# DAI_V1_1.net
KiCad netlist of a schematic drawn in EAGLE
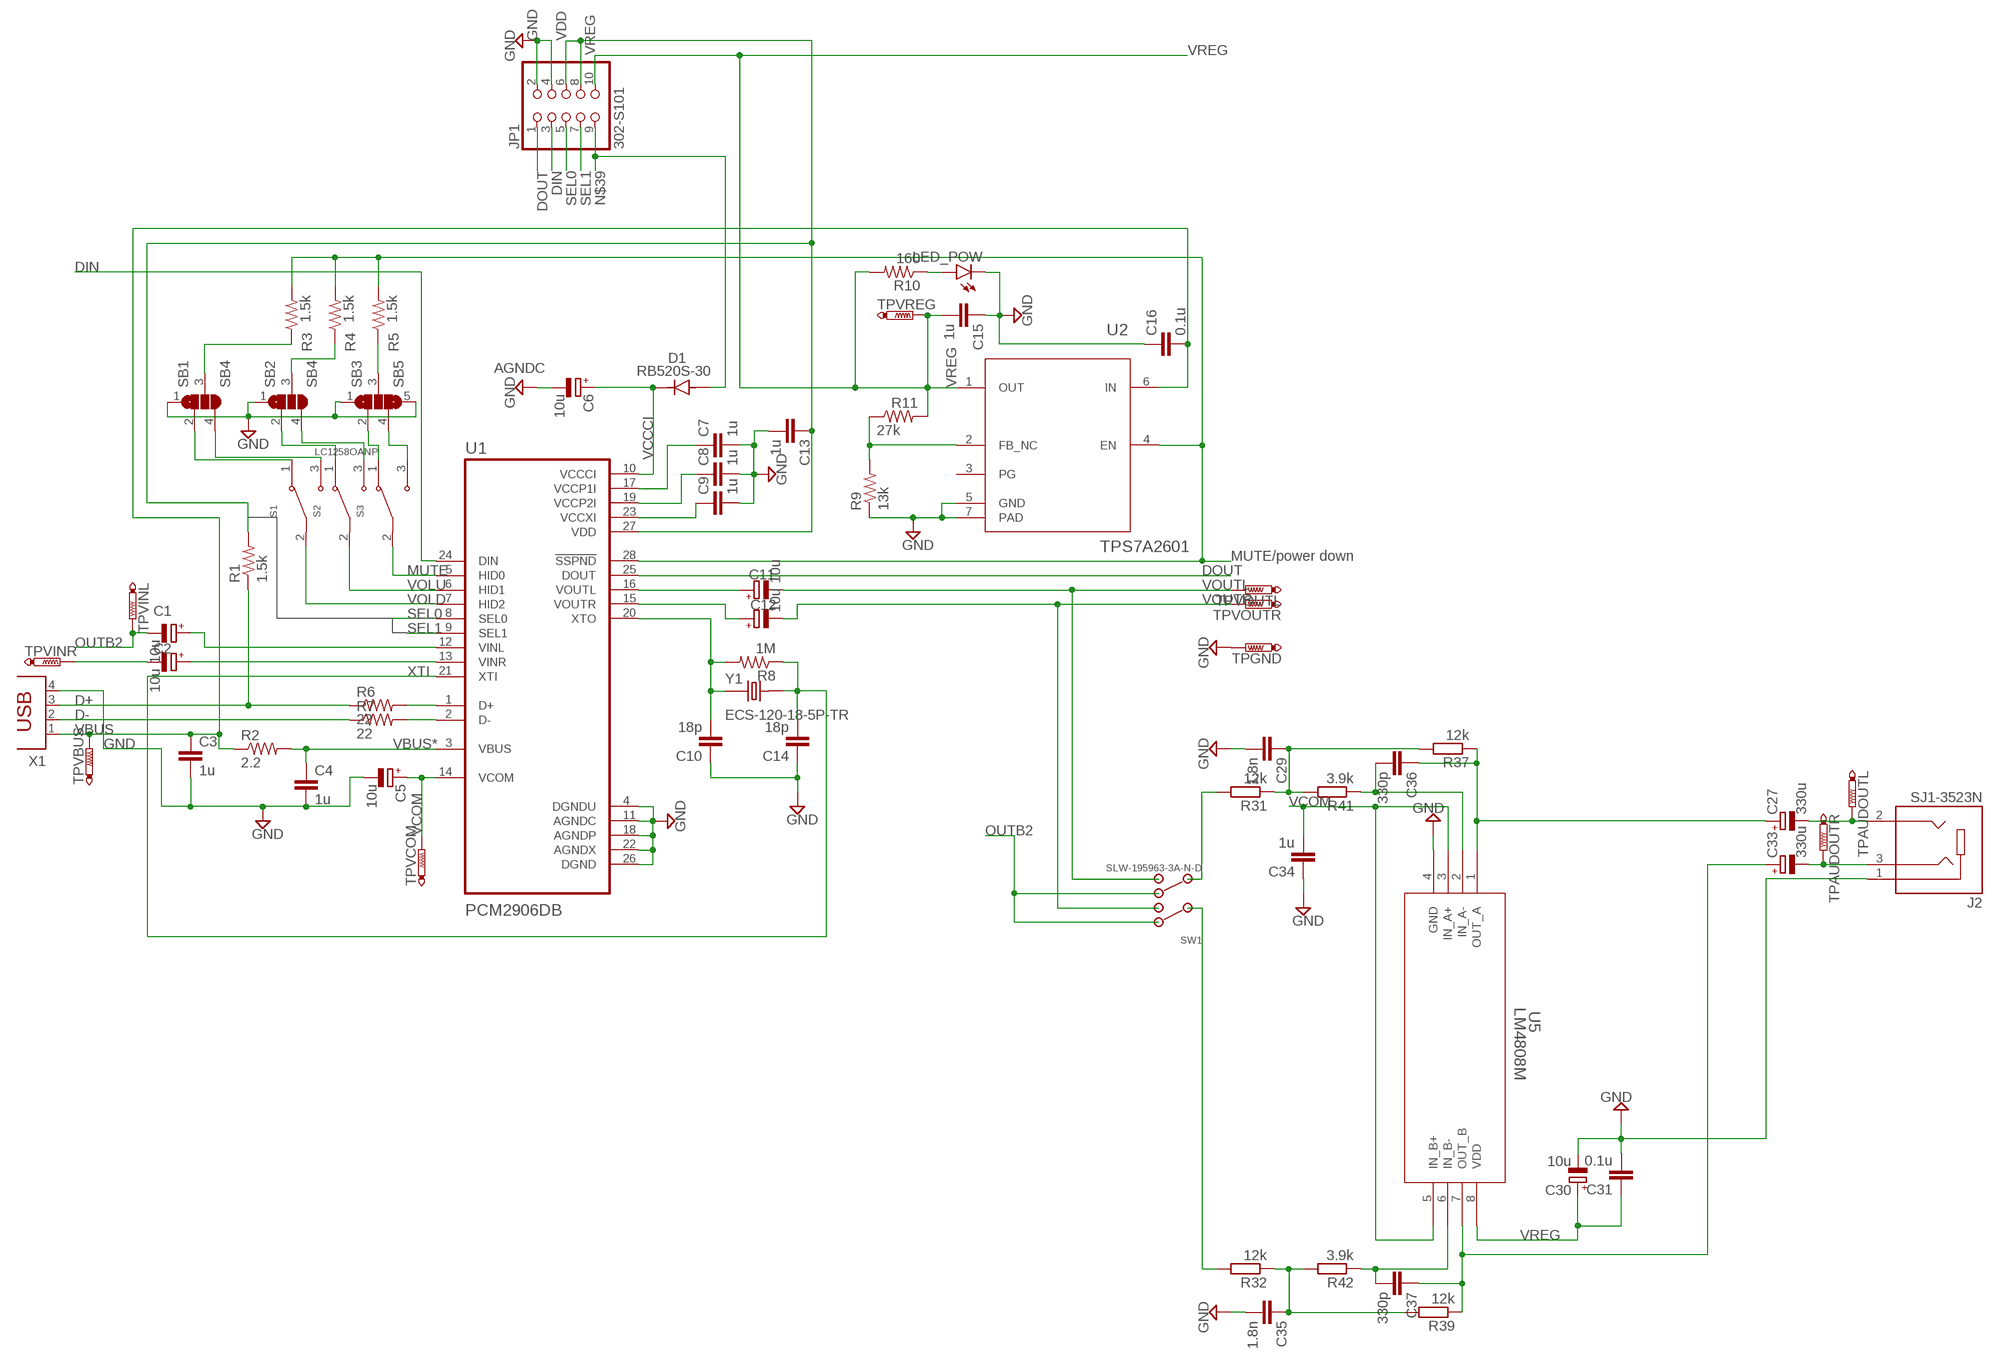
[diagram p0: schematic, sheet 1]
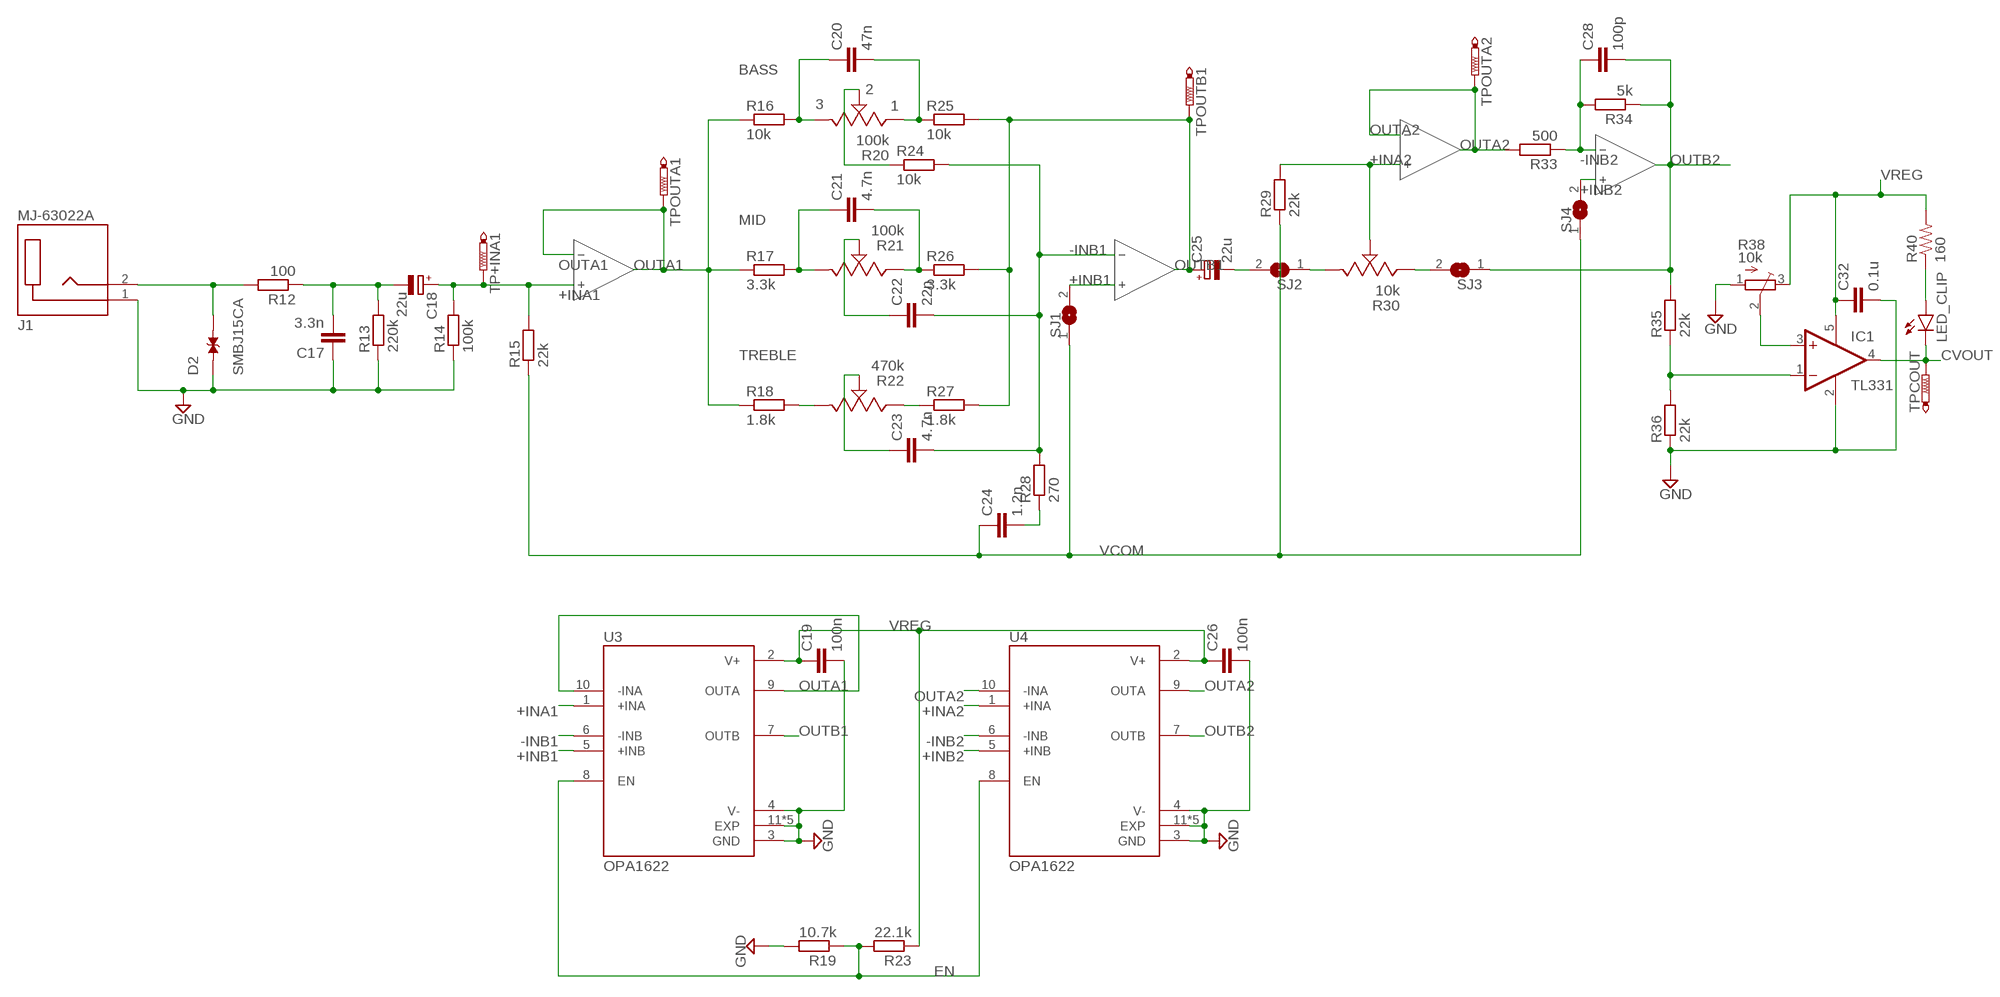
[diagram p1: schematic, sheet 2]

(export (version "E")
  (design (tool "Eeschema 10.0.6"))
  (components
    (comp (ref "C1")
      (value "10u")
      (footprint "eagle-import:PANASONIC_D")
      (libsource (lib "eagle-import") (part "CPOL-EUD"))
    )
    (comp (ref "C2")
      (value "10u")
      (footprint "eagle-import:PANASONIC_D")
      (libsource (lib "eagle-import") (part "CPOL-EUD"))
    )
    (comp (ref "C3")
      (value "1u")
      (footprint "eagle-import:C0805")
      (libsource (lib "eagle-import") (part "C-EUC0805"))
    )
    (comp (ref "C4")
      (value "1u")
      (footprint "eagle-import:C0805")
      (libsource (lib "eagle-import") (part "C-EUC0805"))
    )
    (comp (ref "C5")
      (value "10u")
      (footprint "eagle-import:PANASONIC_B")
      (libsource (lib "eagle-import") (part "CPOL-EUB"))
    )
    (comp (ref "C6")
      (value "10u")
      (footprint "eagle-import:PANASONIC_B")
      (libsource (lib "eagle-import") (part "CPOL-EUB"))
    )
    (comp (ref "C7")
      (value "1u")
      (footprint "eagle-import:C0805")
      (libsource (lib "eagle-import") (part "C-EUC0805"))
    )
    (comp (ref "C8")
      (value "1u")
      (footprint "eagle-import:C0805")
      (libsource (lib "eagle-import") (part "C-EUC0805"))
    )
    (comp (ref "C9")
      (value "1u")
      (footprint "eagle-import:C0805")
      (libsource (lib "eagle-import") (part "C-EUC0805"))
    )
    (comp (ref "C10")
      (value "18p")
      (footprint "eagle-import:C0805")
      (libsource (lib "eagle-import") (part "C-EUC0805"))
    )
    (comp (ref "C11")
      (value "10u")
      (footprint "eagle-import:PANASONIC_D")
      (libsource (lib "eagle-import") (part "CPOL-EUD"))
    )
    (comp (ref "C12")
      (value "10u")
      (footprint "eagle-import:PANASONIC_D")
      (libsource (lib "eagle-import") (part "CPOL-EUD"))
    )
    (comp (ref "C13")
      (value "1u")
      (footprint "eagle-import:C0805")
      (libsource (lib "eagle-import") (part "C-EUC0805"))
    )
    (comp (ref "C14")
      (value "18p")
      (footprint "eagle-import:C0805")
      (libsource (lib "eagle-import") (part "C-EUC0805"))
    )
    (comp (ref "C15")
      (value "1u")
      (footprint "eagle-import:C0805")
      (libsource (lib "eagle-import") (part "C-EUC0805"))
    )
    (comp (ref "C16")
      (value "0.1u")
      (footprint "eagle-import:C0805")
      (libsource (lib "eagle-import") (part "C-EUC0805"))
    )
    (comp (ref "C27")
      (value "330u")
      (footprint "eagle-import:E3,5-10")
      (libsource (lib "eagle-import") (part "CPOL-EUE3.5-10"))
    )
    (comp (ref "C29")
      (value "1.8n")
      (footprint "eagle-import:C1206")
      (libsource (lib "eagle-import") (part "C-EUC1206"))
    )
    (comp (ref "C30")
      (value "10u")
      (footprint "eagle-import:PANASONIC_B")
      (libsource (lib "eagle-import") (part "CPOL-EUB"))
    )
    (comp (ref "C31")
      (value "0.1u")
      (footprint "eagle-import:C0805")
      (libsource (lib "eagle-import") (part "C-EUC0805"))
    )
    (comp (ref "C33")
      (value "330u")
      (footprint "eagle-import:E3,5-10")
      (libsource (lib "eagle-import") (part "CPOL-EUE3.5-10"))
    )
    (comp (ref "C34")
      (value "1u")
      (footprint "eagle-import:C0805")
      (libsource (lib "eagle-import") (part "C-EUC0805"))
    )
    (comp (ref "C35")
      (value "1.8n")
      (footprint "eagle-import:C1206")
      (libsource (lib "eagle-import") (part "C-EUC1206"))
    )
    (comp (ref "C36")
      (value "330p")
      (footprint "eagle-import:C1206")
      (libsource (lib "eagle-import") (part "C-EUC1206"))
    )
    (comp (ref "C37")
      (value "330p")
      (footprint "eagle-import:C1206")
      (libsource (lib "eagle-import") (part "C-EUC1206"))
    )
    (comp (ref "D1")
      (value "RB520S-30")
      (footprint "eagle-import:DIO_RB520S-30")
      (fields (field (name "MF") "Taiwan Semiconductor"))
      (libsource (lib "eagle-import") (part "RB520S-30"))
    )
    (comp (ref "J2")
      (value "SJ1-3523N")
      (footprint "eagle-import:CUI_SJ1-3523N")
      (fields (field (name "MF") "Same Sky"))
      (libsource (lib "eagle-import") (part "SJ1-3523N"))
    )
    (comp (ref "JP1")
      (value "302-S101")
      (footprint "eagle-import:2X05")
      (libsource (lib "eagle-import") (part "PINHD-2X5"))
    )
    (comp (ref "LED_POW")
      (value "LED5MM")
      (footprint "eagle-import:LED5MM")
      (libsource (lib "eagle-import") (part "LED5MM"))
    )
    (comp (ref "R1")
      (value "1.5k")
      (footprint "eagle-import:R0805")
      (libsource (lib "eagle-import") (part "R-US_R0805"))
    )
    (comp (ref "R2")
      (value "2.2")
      (footprint "eagle-import:R0805")
      (libsource (lib "eagle-import") (part "R-US_R0805"))
    )
    (comp (ref "R3")
      (value "1.5k")
      (footprint "eagle-import:R0805")
      (libsource (lib "eagle-import") (part "R-US_R0805"))
    )
    (comp (ref "R4")
      (value "1.5k")
      (footprint "eagle-import:R0805")
      (libsource (lib "eagle-import") (part "R-US_R0805"))
    )
    (comp (ref "R5")
      (value "1.5k")
      (footprint "eagle-import:R0805")
      (libsource (lib "eagle-import") (part "R-US_R0805"))
    )
    (comp (ref "R6")
      (value "22")
      (footprint "eagle-import:R0805")
      (libsource (lib "eagle-import") (part "R-US_R0805"))
    )
    (comp (ref "R7")
      (value "22")
      (footprint "eagle-import:R0805")
      (libsource (lib "eagle-import") (part "R-US_R0805"))
    )
    (comp (ref "R8")
      (value "1M")
      (footprint "eagle-import:R0805")
      (libsource (lib "eagle-import") (part "R-US_R0805"))
    )
    (comp (ref "R9")
      (value "13k")
      (footprint "eagle-import:R0805")
      (libsource (lib "eagle-import") (part "R-US_R0805"))
    )
    (comp (ref "R10")
      (value "160")
      (footprint "eagle-import:R0805")
      (libsource (lib "eagle-import") (part "R-US_R0805"))
    )
    (comp (ref "R11")
      (value "27k")
      (footprint "eagle-import:R0805")
      (libsource (lib "eagle-import") (part "R-US_R0805"))
    )
    (comp (ref "R31")
      (value "12k")
      (footprint "eagle-import:M1206")
      (libsource (lib "eagle-import") (part "R-EU_M1206"))
    )
    (comp (ref "R32")
      (value "12k")
      (footprint "eagle-import:M1206")
      (libsource (lib "eagle-import") (part "R-EU_M1206"))
    )
    (comp (ref "R37")
      (value "12k")
      (footprint "eagle-import:M1206")
      (libsource (lib "eagle-import") (part "R-EU_M1206"))
    )
    (comp (ref "R39")
      (value "12k")
      (footprint "eagle-import:M1206")
      (libsource (lib "eagle-import") (part "R-EU_M1206"))
    )
    (comp (ref "R41")
      (value "3.9k")
      (footprint "eagle-import:M1206")
      (libsource (lib "eagle-import") (part "R-EU_M1206"))
    )
    (comp (ref "R42")
      (value "3.9k")
      (footprint "eagle-import:M1206")
      (libsource (lib "eagle-import") (part "R-EU_M1206"))
    )
    (comp (ref "S1")
      (value "LC1258EENP")
      (footprint "eagle-import:SW_LC1258EENP")
      (fields (field (name "MF") "E-Switch"))
      (libsource (lib "eagle-import") (part "LC1258EENP"))
    )
    (comp (ref "S2")
      (value "LC1258OANP")
      (footprint "eagle-import:SW_LC1258EENP")
      (fields (field (name "MF") "E-Switch") (field (name "MP") "LC1258EENP"))
      (libsource (lib "eagle-import") (part "LC1258EENP"))
    )
    (comp (ref "S3")
      (value "LC1258EENP")
      (footprint "eagle-import:SW_LC1258EENP")
      (fields (field (name "MF") "E-Switch"))
      (libsource (lib "eagle-import") (part "LC1258EENP"))
    )
    (comp (ref "SB1")
      (value "SB4")
      (footprint "eagle-import:SB4")
      (libsource (lib "eagle-import") (part "SB4"))
    )
    (comp (ref "SB2")
      (value "SB4")
      (footprint "eagle-import:SB4")
      (libsource (lib "eagle-import") (part "SB4"))
    )
    (comp (ref "SB3")
      (value "SB5")
      (footprint "eagle-import:SB5")
      (libsource (lib "eagle-import") (part "SB5"))
    )
    (comp (ref "SW1")
      (value "SLW-195963-3A-N-D")
      (footprint "eagle-import:SW-T3-4B-A-A3-S2")
      (libsource (lib "eagle-import") (part "SW-T3-4B-A-A3-S2"))
    )
    (comp (ref "TPAUDOUTL")
      (value "PTR1PAD1-13")
      (footprint "eagle-import:P1-13")
      (libsource (lib "eagle-import") (part "PTR1PAD1-13"))
    )
    (comp (ref "TPAUDOUTR")
      (value "PTR1PAD1-13")
      (footprint "eagle-import:P1-13")
      (libsource (lib "eagle-import") (part "PTR1PAD1-13"))
    )
    (comp (ref "TPGND")
      (value "PTR1PAD1-13")
      (footprint "eagle-import:P1-13")
      (libsource (lib "eagle-import") (part "PTR1PAD1-13"))
    )
    (comp (ref "TPVBUS")
      (value "PTR1PAD1-13")
      (footprint "eagle-import:P1-13")
      (libsource (lib "eagle-import") (part "PTR1PAD1-13"))
    )
    (comp (ref "TPVCOM")
      (value "PTR1PAD1-13")
      (footprint "eagle-import:P1-13")
      (libsource (lib "eagle-import") (part "PTR1PAD1-13"))
    )
    (comp (ref "TPVINL")
      (value "PTR1PAD1-13")
      (footprint "eagle-import:P1-13")
      (libsource (lib "eagle-import") (part "PTR1PAD1-13"))
    )
    (comp (ref "TPVINR")
      (value "PTR1PAD1-13")
      (footprint "eagle-import:P1-13")
      (libsource (lib "eagle-import") (part "PTR1PAD1-13"))
    )
    (comp (ref "TPVOUTL")
      (value "PTR1PAD1-13")
      (footprint "eagle-import:P1-13")
      (libsource (lib "eagle-import") (part "PTR1PAD1-13"))
    )
    (comp (ref "TPVOUTR")
      (value "PTR1PAD1-13")
      (footprint "eagle-import:P1-13")
      (libsource (lib "eagle-import") (part "PTR1PAD1-13"))
    )
    (comp (ref "TPVREG")
      (value "PTR1PAD1-13")
      (footprint "eagle-import:P1-13")
      (libsource (lib "eagle-import") (part "PTR1PAD1-13"))
    )
    (comp (ref "U1")
      (value "PCM2906DB")
      (footprint "eagle-import:SOP65P780X200-28N")
      (fields (field (name "MF") "Texas Instruments"))
      (libsource (lib "eagle-import") (part "PCM2906DB"))
    )
    (comp (ref "U2")
      (value "TPS7A2601")
      (footprint "eagle-import:DRV0006A_NV")
      (fields
        (field (name "MANUFACTURER_PART_NUMBER") "TPS7A2601DRVR")
        (field (name "COPYRIGHT") "Copyright (C) 2025 Ultra Librarian. All rights reserved.")
      )
      (libsource (lib "eagle-import") (part "TPS7A2601DRVRDRV0006A_NV"))
    )
    (comp (ref "U5")
      (value "LM4808M")
      (footprint "eagle-import:M08A")
      (fields
        (field (name "MANUFACTURER_PART_NUMBER") "LM4808M/NOPB")
        (field (name "COPYRIGHT") "Copyright (C) 2025 Ultra Librarian. All rights reserved.")
      )
      (libsource (lib "eagle-import") (part "LM4808M/NOPB"))
    )
    (comp (ref "X1")
      (value "PN61729")
      (footprint "eagle-import:PN61729")
      (libsource (lib "eagle-import") (part "PN61729"))
    )
    (comp (ref "Y1")
      (value "ECS-120-18-5P-TR")
      (footprint "eagle-import:XTAL_ECS-120-18-5P-TR")
      (fields (field (name "MF") "ECS International"))
      (libsource (lib "eagle-import") (part "ECS-120-18-5P-TR"))
    )
    (comp (ref "C17")
      (value "3.3n")
      (footprint "eagle-import:C1206")
      (libsource (lib "eagle-import") (part "C-EUC1206"))
    )
    (comp (ref "C18")
      (value "22u")
      (footprint "eagle-import:PANASONIC_D")
      (libsource (lib "eagle-import") (part "CPOL-EUD"))
    )
    (comp (ref "C19")
      (value "100n")
      (footprint "eagle-import:C0805")
      (libsource (lib "eagle-import") (part "C-EUC0805"))
    )
    (comp (ref "C20")
      (value "47n")
      (footprint "eagle-import:C1206")
      (libsource (lib "eagle-import") (part "C-EUC1206"))
    )
    (comp (ref "C21")
      (value "4.7n")
      (footprint "eagle-import:C1206")
      (libsource (lib "eagle-import") (part "C-EUC1206"))
    )
    (comp (ref "C22")
      (value "22n")
      (footprint "eagle-import:C1206")
      (libsource (lib "eagle-import") (part "C-EUC1206"))
    )
    (comp (ref "C23")
      (value "4.7n")
      (footprint "eagle-import:C1206")
      (libsource (lib "eagle-import") (part "C-EUC1206"))
    )
    (comp (ref "C24")
      (value "1.2n")
      (footprint "eagle-import:C1206")
      (libsource (lib "eagle-import") (part "C-EUC1206"))
    )
    (comp (ref "C25")
      (value "22u")
      (footprint "eagle-import:PANASONIC_D")
      (libsource (lib "eagle-import") (part "CPOL-EUD"))
    )
    (comp (ref "C26")
      (value "100n")
      (footprint "eagle-import:C0805")
      (libsource (lib "eagle-import") (part "C-EUC0805"))
    )
    (comp (ref "C28")
      (value "100p")
      (footprint "eagle-import:C1206")
      (libsource (lib "eagle-import") (part "C-EUC1206"))
    )
    (comp (ref "C32")
      (value "0.1u")
      (footprint "eagle-import:C0805")
      (libsource (lib "eagle-import") (part "C-EUC0805"))
    )
    (comp (ref "D2")
      (value "SMBJ15CA")
      (footprint "eagle-import:DIOM4336X265N")
      (fields (field (name "MF") "Taiwan Semiconductor"))
      (libsource (lib "eagle-import") (part "SMBJ15CA"))
    )
    (comp (ref "IC1")
      (value "TL331")
      (footprint "eagle-import:DBV-R-PDSO-G5")
      (libsource (lib "eagle-import") (part "TL331"))
    )
    (comp (ref "J1")
      (value "MJ-63022A")
      (footprint "eagle-import:CUI_MJ-63022A")
      (fields (field (name "MF") "Same Sky"))
      (libsource (lib "eagle-import") (part "MJ-63022A"))
    )
    (comp (ref "LED_CLIP")
      (value "LED5MM")
      (footprint "eagle-import:LED5MM")
      (libsource (lib "eagle-import") (part "LED5MM"))
    )
    (comp (ref "R12")
      (value "100")
      (footprint "eagle-import:M1206")
      (libsource (lib "eagle-import") (part "R-EU_M1206"))
    )
    (comp (ref "R13")
      (value "220k")
      (footprint "eagle-import:M1206")
      (libsource (lib "eagle-import") (part "R-EU_M1206"))
    )
    (comp (ref "R14")
      (value "100k")
      (footprint "eagle-import:M1206")
      (libsource (lib "eagle-import") (part "R-EU_M1206"))
    )
    (comp (ref "R15")
      (value "22k")
      (footprint "eagle-import:M1206")
      (libsource (lib "eagle-import") (part "R-EU_M1206"))
    )
    (comp (ref "R16")
      (value "10k")
      (footprint "eagle-import:M1206")
      (libsource (lib "eagle-import") (part "R-EU_M1206"))
    )
    (comp (ref "R17")
      (value "3.3k")
      (footprint "eagle-import:M1206")
      (libsource (lib "eagle-import") (part "R-EU_M1206"))
    )
    (comp (ref "R18")
      (value "1.8k")
      (footprint "eagle-import:M1206")
      (libsource (lib "eagle-import") (part "R-EU_M1206"))
    )
    (comp (ref "R19")
      (value "10.7k")
      (footprint "eagle-import:R1206")
      (libsource (lib "eagle-import") (part "R-EU_R1206"))
    )
    (comp (ref "R20")
      (value "100k")
      (footprint "eagle-import:POT_PTN16-A100125K1B1")
      (fields (field (name "MF") "Same Sky") (field (name "MP") "PTN16-A100125K1B1"))
      (libsource (lib "eagle-import") (part "PTN16-A100125K1B1"))
    )
    (comp (ref "R21")
      (value "100k")
      (footprint "eagle-import:POT_PTN16-A100125K1B1")
      (fields (field (name "MF") "Same Sky") (field (name "MP") "PTN16-A100125K1B1"))
      (libsource (lib "eagle-import") (part "PTN16-A100125K1B1"))
    )
    (comp (ref "R22")
      (value "470k")
      (footprint "eagle-import:POT_PTN16-A100125K1B1")
      (fields (field (name "MF") "Same Sky") (field (name "MP") "PTN16-A100125K1B1"))
      (libsource (lib "eagle-import") (part "PTN16-A100125K1B1"))
    )
    (comp (ref "R23")
      (value "22.1k")
      (footprint "eagle-import:R1206")
      (libsource (lib "eagle-import") (part "R-EU_R1206"))
    )
    (comp (ref "R24")
      (value "10k")
      (footprint "eagle-import:M1206")
      (libsource (lib "eagle-import") (part "R-EU_M1206"))
    )
    (comp (ref "R25")
      (value "10k")
      (footprint "eagle-import:M1206")
      (libsource (lib "eagle-import") (part "R-EU_M1206"))
    )
    (comp (ref "R26")
      (value "3.3k")
      (footprint "eagle-import:M1206")
      (libsource (lib "eagle-import") (part "R-EU_M1206"))
    )
    (comp (ref "R27")
      (value "1.8k")
      (footprint "eagle-import:M1206")
      (libsource (lib "eagle-import") (part "R-EU_M1206"))
    )
    (comp (ref "R28")
      (value "270")
      (footprint "eagle-import:M1206")
      (libsource (lib "eagle-import") (part "R-EU_M1206"))
    )
    (comp (ref "R29")
      (value "22k")
      (footprint "eagle-import:M1206")
      (libsource (lib "eagle-import") (part "R-EU_M1206"))
    )
    (comp (ref "R30")
      (value "10k")
      (footprint "eagle-import:POT_PTN16-A100125K1B1")
      (fields (field (name "MF") "Same Sky") (field (name "MP") "PTN16-A100125K1B1"))
      (libsource (lib "eagle-import") (part "PTN16-A100125K1B1"))
    )
    (comp (ref "R33")
      (value "500")
      (footprint "eagle-import:M1206")
      (libsource (lib "eagle-import") (part "R-EU_M1206"))
    )
    (comp (ref "R34")
      (value "5k")
      (footprint "eagle-import:M1206")
      (libsource (lib "eagle-import") (part "R-EU_M1206"))
    )
    (comp (ref "R35")
      (value "22k")
      (footprint "eagle-import:M1206")
      (libsource (lib "eagle-import") (part "R-EU_M1206"))
    )
    (comp (ref "R36")
      (value "22k")
      (footprint "eagle-import:M1206")
      (libsource (lib "eagle-import") (part "R-EU_M1206"))
    )
    (comp (ref "R38")
      (value "10k")
      (footprint "eagle-import:601030_AVX")
      (fields
        (field (name "MANUFACTURER_PART_NUMBER") "601030")
        (field (name "COPYRIGHT") "Copyright (C) 2025 Ultra Librarian. All rights reserved.")
      )
      (libsource (lib "eagle-import") (part "601030"))
    )
    (comp (ref "R40")
      (value "160")
      (footprint "eagle-import:R0805")
      (libsource (lib "eagle-import") (part "R-US_R0805"))
    )
    (comp (ref "SJ1")
      (value "SJW")
      (footprint "eagle-import:SJW")
      (libsource (lib "eagle-import") (part "SJW"))
    )
    (comp (ref "SJ2")
      (value "SJW")
      (footprint "eagle-import:SJW")
      (libsource (lib "eagle-import") (part "SJW"))
    )
    (comp (ref "SJ3")
      (value "SJW")
      (footprint "eagle-import:SJW")
      (libsource (lib "eagle-import") (part "SJW"))
    )
    (comp (ref "SJ4")
      (value "SJW")
      (footprint "eagle-import:SJW")
      (libsource (lib "eagle-import") (part "SJW"))
    )
    (comp (ref "TP+INA1")
      (value "PTR1PAD1-13")
      (footprint "eagle-import:P1-13")
      (libsource (lib "eagle-import") (part "PTR1PAD1-13"))
    )
    (comp (ref "TPCOUT")
      (value "PTR1PAD1-13")
      (footprint "eagle-import:P1-13")
      (libsource (lib "eagle-import") (part "PTR1PAD1-13"))
    )
    (comp (ref "TPOUTA1")
      (value "PTR1PAD1-13")
      (footprint "eagle-import:P1-13")
      (libsource (lib "eagle-import") (part "PTR1PAD1-13"))
    )
    (comp (ref "TPOUTA2")
      (value "PTR1PAD1-13")
      (footprint "eagle-import:P1-13")
      (libsource (lib "eagle-import") (part "PTR1PAD1-13"))
    )
    (comp (ref "TPOUTB1")
      (value "PTR1PAD1-13")
      (footprint "eagle-import:P1-13")
      (libsource (lib "eagle-import") (part "PTR1PAD1-13"))
    )
    (comp (ref "U3")
      (value "OPA1622")
      (footprint "eagle-import:IC_OPA1622IDRCR")
      (fields (field (name "MF") "Texas Instruments") (field (name "MP") "OPA1622IDRCR"))
      (libsource (lib "eagle-import") (part "OPA1622IDRCR"))
    )
    (comp (ref "U4")
      (value "OPA1622")
      (footprint "eagle-import:IC_OPA1622IDRCR")
      (fields (field (name "MF") "Texas Instruments") (field (name "MP") "OPA1622IDRCR"))
      (libsource (lib "eagle-import") (part "OPA1622IDRCR"))
    )
  )
  (nets
    (net (code "1") (name "+INA1") (class "Default")
      (node (ref "C18") (pin "+") (pinfunction "+_+") (pintype "passive"))
      (node (ref "R14") (pin "2") (pinfunction "2_2") (pintype "passive"))
      (node (ref "R15") (pin "2") (pinfunction "2_2") (pintype "passive"))
      (node (ref "TP+INA1") (pin "TP") (pinfunction "TP_TP") (pintype "input"))
      (node (ref "U3") (pin "1") (pinfunction "+INA_1") (pintype "input"))
    )
    (net (code "2") (name "+INA2") (class "Default")
      (node (ref "R29") (pin "2") (pinfunction "2_2") (pintype "passive"))
      (node (ref "R30") (pin "2") (pinfunction "2_2") (pintype "passive"))
      (node (ref "U4") (pin "1") (pinfunction "+INA_1") (pintype "input"))
    )
    (net (code "3") (name "+INB1") (class "Default")
      (node (ref "SJ1") (pin "2") (pinfunction "2_2") (pintype "passive"))
      (node (ref "U3") (pin "5") (pinfunction "+INB_5") (pintype "input"))
    )
    (net (code "4") (name "+INB2") (class "Default")
      (node (ref "SJ4") (pin "2") (pinfunction "2_2") (pintype "passive"))
      (node (ref "U4") (pin "5") (pinfunction "+INB_5") (pintype "input"))
    )
    (net (code "5") (name "-INB1") (class "Default")
      (node (ref "C22") (pin "2") (pinfunction "2_2") (pintype "passive"))
      (node (ref "C23") (pin "2") (pinfunction "2_2") (pintype "passive"))
      (node (ref "R24") (pin "2") (pinfunction "2_2") (pintype "passive"))
      (node (ref "R28") (pin "2") (pinfunction "2_2") (pintype "passive"))
      (node (ref "U3") (pin "6") (pinfunction "-INB_6") (pintype "input"))
    )
    (net (code "6") (name "-INB2") (class "Default")
      (node (ref "C28") (pin "1") (pinfunction "1_1") (pintype "passive"))
      (node (ref "R33") (pin "1") (pinfunction "1_1") (pintype "passive"))
      (node (ref "R34") (pin "2") (pinfunction "2_2") (pintype "passive"))
      (node (ref "U4") (pin "6") (pinfunction "-INB_6") (pintype "input"))
    )
    (net (code "7") (name "CVOUT") (class "Default")
      (node (ref "IC1") (pin "4") (pinfunction "OUT_4") (pintype "output"))
      (node (ref "LED_CLIP") (pin "K") (pinfunction "C_K") (pintype "passive"))
      (node (ref "TPCOUT") (pin "TP") (pinfunction "TP_TP") (pintype "input"))
    )
    (net (code "8") (name "D+") (class "Default")
      (node (ref "R1") (pin "1") (pinfunction "1_1") (pintype "passive"))
      (node (ref "R6") (pin "1") (pinfunction "1_1") (pintype "passive"))
      (node (ref "X1") (pin "3") (pinfunction "3_3") (pintype "passive"))
    )
    (net (code "9") (name "D-") (class "Default")
      (node (ref "R7") (pin "1") (pinfunction "1_1") (pintype "passive"))
      (node (ref "X1") (pin "2") (pinfunction "2_2") (pintype "passive"))
    )
    (net (code "10") (name "DIN") (class "Default")
      (node (ref "JP1") (pin "3") (pinfunction "3_3") (pintype "passive"))
      (node (ref "U1") (pin "24") (pinfunction "DIN_24") (pintype "input"))
    )
    (net (code "11") (name "DOUT") (class "Default")
      (node (ref "JP1") (pin "1") (pinfunction "1_1") (pintype "passive"))
      (node (ref "U1") (pin "25") (pinfunction "DOUT_25") (pintype "output"))
    )
    (net (code "12") (name "EN") (class "Default")
      (node (ref "R19") (pin "1") (pinfunction "1_1") (pintype "passive"))
      (node (ref "R23") (pin "2") (pinfunction "2_2") (pintype "passive"))
      (node (ref "U3") (pin "8") (pinfunction "EN_8") (pintype "input"))
      (node (ref "U4") (pin "8") (pinfunction "EN_8") (pintype "input"))
    )
    (net (code "13") (name "GND") (class "Default")
      (node (ref "C10") (pin "1") (pinfunction "1_1") (pintype "passive"))
      (node (ref "C13") (pin "2") (pinfunction "2_2") (pintype "passive"))
      (node (ref "C14") (pin "1") (pinfunction "1_1") (pintype "passive"))
      (node (ref "C15") (pin "1") (pinfunction "1_1") (pintype "passive"))
      (node (ref "C16") (pin "1") (pinfunction "1_1") (pintype "passive"))
      (node (ref "C17") (pin "1") (pinfunction "1_1") (pintype "passive"))
      (node (ref "C19") (pin "2") (pinfunction "2_2") (pintype "passive"))
      (node (ref "C26") (pin "2") (pinfunction "2_2") (pintype "passive"))
      (node (ref "C29") (pin "2") (pinfunction "2_2") (pintype "passive"))
      (node (ref "C3") (pin "2") (pinfunction "2_2") (pintype "passive"))
      (node (ref "C30") (pin "-") (pinfunction "-_-") (pintype "passive"))
      (node (ref "C31") (pin "2") (pinfunction "2_2") (pintype "passive"))
      (node (ref "C32") (pin "2") (pinfunction "2_2") (pintype "passive"))
      (node (ref "C34") (pin "1") (pinfunction "1_1") (pintype "passive"))
      (node (ref "C35") (pin "2") (pinfunction "2_2") (pintype "passive"))
      (node (ref "C4") (pin "2") (pinfunction "2_2") (pintype "passive"))
      (node (ref "C5") (pin "-") (pinfunction "-_-") (pintype "passive"))
      (node (ref "C6") (pin "-") (pinfunction "-_-") (pintype "passive"))
      (node (ref "C7") (pin "2") (pinfunction "2_2") (pintype "passive"))
      (node (ref "C8") (pin "2") (pinfunction "2_2") (pintype "passive"))
      (node (ref "C9") (pin "2") (pinfunction "2_2") (pintype "passive"))
      (node (ref "D2") (pin "1") (pinfunction "1_1") (pintype "passive"))
      (node (ref "IC1") (pin "2") (pinfunction "GND_2") (pintype "power_in"))
      (node (ref "J1") (pin "1") (pinfunction "SLEEVE_1") (pintype "passive"))
      (node (ref "J2") (pin "1") (pinfunction "1_1") (pintype "passive"))
      (node (ref "JP1") (pin "2") (pinfunction "2_2") (pintype "passive"))
      (node (ref "JP1") (pin "4") (pinfunction "4_4") (pintype "passive"))
      (node (ref "LED_POW") (pin "K") (pinfunction "C_K") (pintype "passive"))
      (node (ref "R13") (pin "1") (pinfunction "1_1") (pintype "passive"))
      (node (ref "R14") (pin "1") (pinfunction "1_1") (pintype "passive"))
      (node (ref "R19") (pin "2") (pinfunction "2_2") (pintype "passive"))
      (node (ref "R36") (pin "1") (pinfunction "1_1") (pintype "passive"))
      (node (ref "R38") (pin "1") (pinfunction "A_1") (pintype "passive"))
      (node (ref "R9") (pin "1") (pinfunction "1_1") (pintype "passive"))
      (node (ref "SB1") (pin "1") (pinfunction "1_1") (pintype "passive"))
      (node (ref "SB2") (pin "1") (pinfunction "1_1") (pintype "passive"))
      (node (ref "SB3") (pin "1") (pinfunction "1_1") (pintype "passive"))
      (node (ref "SB3") (pin "5") (pinfunction "5_5") (pintype "passive"))
      (node (ref "TPGND") (pin "TP") (pinfunction "TP_TP") (pintype "input"))
      (node (ref "U1") (pin "11") (pinfunction "AGNDC_11") (pintype "power_in"))
      (node (ref "U1") (pin "18") (pinfunction "AGNDP_18") (pintype "power_in"))
      (node (ref "U1") (pin "22") (pinfunction "AGNDX_22") (pintype "power_in"))
      (node (ref "U1") (pin "26") (pinfunction "DGND_26") (pintype "power_in"))
      (node (ref "U1") (pin "4") (pinfunction "DGNDU_4") (pintype "power_in"))
      (node (ref "U2") (pin "5") (pinfunction "GND_5") (pintype "power_in"))
      (node (ref "U2") (pin "7") (pinfunction "PAD_7") (pintype "passive"))
      (node (ref "U3") (pin "11") (pinfunction "EXP_11") (pintype "power_in"))
      (node (ref "U3") (pin "12") (pinfunction "EXP_12") (pintype "power_in"))
      (node (ref "U3") (pin "13") (pinfunction "EXP_13") (pintype "power_in"))
      (node (ref "U3") (pin "14") (pinfunction "EXP_14") (pintype "power_in"))
      (node (ref "U3") (pin "15") (pinfunction "EXP_15") (pintype "power_in"))
      (node (ref "U3") (pin "3") (pinfunction "GND_3") (pintype "power_in"))
      (node (ref "U3") (pin "4") (pinfunction "V-_4") (pintype "power_in"))
      (node (ref "U4") (pin "11") (pinfunction "EXP_11") (pintype "power_in"))
      (node (ref "U4") (pin "12") (pinfunction "EXP_12") (pintype "power_in"))
      (node (ref "U4") (pin "13") (pinfunction "EXP_13") (pintype "power_in"))
      (node (ref "U4") (pin "14") (pinfunction "EXP_14") (pintype "power_in"))
      (node (ref "U4") (pin "15") (pinfunction "EXP_15") (pintype "power_in"))
      (node (ref "U4") (pin "3") (pinfunction "GND_3") (pintype "power_in"))
      (node (ref "U4") (pin "4") (pinfunction "V-_4") (pintype "power_in"))
      (node (ref "U5") (pin "4") (pinfunction "GND_4") (pintype "power_in"))
      (node (ref "X1") (pin "4") (pinfunction "4_4") (pintype "passive"))
    )
    (net (code "14") (name "MUTE") (class "Default")
      (node (ref "S3") (pin "2") (pinfunction "COM_2") (pintype "passive"))
      (node (ref "U1") (pin "5") (pinfunction "HID0_5") (pintype "input"))
    )
    (net (code "15") (name "N$39") (class "Default")
      (node (ref "D1") (pin "A") (pinfunction "A_A") (pintype "passive"))
      (node (ref "JP1") (pin "9") (pinfunction "9_9") (pintype "passive"))
    )
    (net (code "16") (name "Net-(C2-Pad-)") (class "Default")
      (node (ref "C2") (pin "-") (pinfunction "-_-") (pintype "passive"))
      (node (ref "TPVINR") (pin "TP") (pinfunction "TP_TP") (pintype "input"))
    )
    (net (code "17") (name "Net-(C17-Pad2)") (class "Default")
      (node (ref "C17") (pin "2") (pinfunction "2_2") (pintype "passive"))
      (node (ref "C18") (pin "-") (pinfunction "-_-") (pintype "passive"))
      (node (ref "R12") (pin "1") (pinfunction "1_1") (pintype "passive"))
      (node (ref "R13") (pin "2") (pinfunction "2_2") (pintype "passive"))
    )
    (net (code "18") (name "Net-(C20-Pad1)") (class "Default")
      (node (ref "C20") (pin "1") (pinfunction "1_1") (pintype "passive"))
      (node (ref "R16") (pin "2") (pinfunction "2_2") (pintype "passive"))
      (node (ref "R20") (pin "3") (pinfunction "3_3") (pintype "passive"))
    )
    (net (code "19") (name "Net-(C20-Pad2)") (class "Default")
      (node (ref "C20") (pin "2") (pinfunction "2_2") (pintype "passive"))
      (node (ref "R20") (pin "1") (pinfunction "1_1") (pintype "passive"))
      (node (ref "R25") (pin "1") (pinfunction "1_1") (pintype "passive"))
    )
    (net (code "20") (name "Net-(C21-Pad1)") (class "Default")
      (node (ref "C21") (pin "1") (pinfunction "1_1") (pintype "passive"))
      (node (ref "R17") (pin "2") (pinfunction "2_2") (pintype "passive"))
      (node (ref "R21") (pin "3") (pinfunction "3_3") (pintype "passive"))
    )
    (net (code "21") (name "Net-(C21-Pad2)") (class "Default")
      (node (ref "C21") (pin "2") (pinfunction "2_2") (pintype "passive"))
      (node (ref "R21") (pin "1") (pinfunction "1_1") (pintype "passive"))
      (node (ref "R26") (pin "1") (pinfunction "1_1") (pintype "passive"))
    )
    (net (code "22") (name "Net-(C22-Pad1)") (class "Default")
      (node (ref "C22") (pin "1") (pinfunction "1_1") (pintype "passive"))
      (node (ref "R21") (pin "2") (pinfunction "2_2") (pintype "passive"))
    )
    (net (code "23") (name "Net-(C23-Pad1)") (class "Default")
      (node (ref "C23") (pin "1") (pinfunction "1_1") (pintype "passive"))
      (node (ref "R22") (pin "2") (pinfunction "2_2") (pintype "passive"))
    )
    (net (code "24") (name "Net-(C24-Pad2)") (class "Default")
      (node (ref "C24") (pin "2") (pinfunction "2_2") (pintype "passive"))
      (node (ref "R28") (pin "1") (pinfunction "1_1") (pintype "passive"))
    )
    (net (code "25") (name "Net-(C25-Pad-)") (class "Default")
      (node (ref "C25") (pin "-") (pinfunction "-_-") (pintype "passive"))
      (node (ref "SJ2") (pin "2") (pinfunction "2_2") (pintype "passive"))
    )
    (net (code "26") (name "Net-(C27-Pad-)") (class "Default")
      (node (ref "C27") (pin "-") (pinfunction "-_-") (pintype "passive"))
      (node (ref "J2") (pin "2") (pinfunction "2_2") (pintype "passive"))
      (node (ref "TPAUDOUTL") (pin "TP") (pinfunction "TP_TP") (pintype "input"))
    )
    (net (code "27") (name "Net-(C29-Pad1)") (class "Default")
      (node (ref "C29") (pin "1") (pinfunction "1_1") (pintype "passive"))
      (node (ref "R31") (pin "1") (pinfunction "1_1") (pintype "passive"))
      (node (ref "R37") (pin "2") (pinfunction "2_2") (pintype "passive"))
      (node (ref "R41") (pin "2") (pinfunction "2_2") (pintype "passive"))
    )
    (net (code "28") (name "Net-(C33-Pad-)") (class "Default")
      (node (ref "C33") (pin "-") (pinfunction "-_-") (pintype "passive"))
      (node (ref "J2") (pin "3") (pinfunction "3_3") (pintype "passive"))
      (node (ref "TPAUDOUTR") (pin "TP") (pinfunction "TP_TP") (pintype "input"))
    )
    (net (code "29") (name "Net-(C35-Pad1)") (class "Default")
      (node (ref "C35") (pin "1") (pinfunction "1_1") (pintype "passive"))
      (node (ref "R32") (pin "1") (pinfunction "1_1") (pintype "passive"))
      (node (ref "R39") (pin "2") (pinfunction "2_2") (pintype "passive"))
      (node (ref "R42") (pin "2") (pinfunction "2_2") (pintype "passive"))
    )
    (net (code "30") (name "Net-(IC1-+IN)") (class "Default")
      (node (ref "IC1") (pin "3") (pinfunction "+IN_3") (pintype "input"))
      (node (ref "R38") (pin "2") (pinfunction "S_2") (pintype "passive"))
    )
    (net (code "31") (name "Net-(IC1--IN)") (class "Default")
      (node (ref "IC1") (pin "1") (pinfunction "-IN_1") (pintype "input"))
      (node (ref "R35") (pin "1") (pinfunction "1_1") (pintype "passive"))
      (node (ref "R36") (pin "2") (pinfunction "2_2") (pintype "passive"))
    )
    (net (code "32") (name "Net-(J1-TIP)") (class "Default")
      (node (ref "D2") (pin "2") (pinfunction "2_2") (pintype "passive"))
      (node (ref "J1") (pin "2") (pinfunction "TIP_2") (pintype "passive"))
      (node (ref "R12") (pin "2") (pinfunction "2_2") (pintype "passive"))
    )
    (net (code "33") (name "Net-(LED_CLIP-PadA)") (class "Default")
      (node (ref "LED_CLIP") (pin "A") (pinfunction "A_A") (pintype "passive"))
      (node (ref "R40") (pin "1") (pinfunction "1_1") (pintype "passive"))
    )
    (net (code "34") (name "Net-(LED_POW-PadA)") (class "Default")
      (node (ref "LED_POW") (pin "A") (pinfunction "A_A") (pintype "passive"))
      (node (ref "R10") (pin "1") (pinfunction "1_1") (pintype "passive"))
    )
    (net (code "35") (name "Net-(R3-Pad1)") (class "Default")
      (node (ref "R3") (pin "1") (pinfunction "1_1") (pintype "passive"))
      (node (ref "SB1") (pin "3") (pinfunction "3_3") (pintype "passive"))
    )
    (net (code "36") (name "Net-(R4-Pad1)") (class "Default")
      (node (ref "R4") (pin "1") (pinfunction "1_1") (pintype "passive"))
      (node (ref "SB2") (pin "3") (pinfunction "3_3") (pintype "passive"))
    )
    (net (code "37") (name "Net-(R5-Pad1)") (class "Default")
      (node (ref "R5") (pin "1") (pinfunction "1_1") (pintype "passive"))
      (node (ref "SB3") (pin "3") (pinfunction "3_3") (pintype "passive"))
    )
    (net (code "38") (name "Net-(R18-Pad2)") (class "Default")
      (node (ref "R18") (pin "2") (pinfunction "2_2") (pintype "passive"))
      (node (ref "R22") (pin "3") (pinfunction "3_3") (pintype "passive"))
    )
    (net (code "39") (name "Net-(R20-Pad2)") (class "Default")
      (node (ref "R20") (pin "2") (pinfunction "2_2") (pintype "passive"))
      (node (ref "R24") (pin "1") (pinfunction "1_1") (pintype "passive"))
    )
    (net (code "40") (name "Net-(R22-Pad1)") (class "Default")
      (node (ref "R22") (pin "1") (pinfunction "1_1") (pintype "passive"))
      (node (ref "R27") (pin "1") (pinfunction "1_1") (pintype "passive"))
    )
    (net (code "41") (name "Net-(R30-Pad1)") (class "Default")
      (node (ref "R30") (pin "1") (pinfunction "1_1") (pintype "passive"))
      (node (ref "SJ3") (pin "2") (pinfunction "2_2") (pintype "passive"))
    )
    (net (code "42") (name "Net-(R30-Pad3)") (class "Default")
      (node (ref "R30") (pin "3") (pinfunction "3_3") (pintype "passive"))
      (node (ref "SJ2") (pin "1") (pinfunction "1_1") (pintype "passive"))
    )
    (net (code "43") (name "Net-(R31-Pad2)") (class "Default")
      (node (ref "R31") (pin "2") (pinfunction "2_2") (pintype "passive"))
      (node (ref "SW1") (pin "5") (pinfunction "5_5") (pintype "bidirectional"))
    )
    (net (code "44") (name "Net-(R32-Pad2)") (class "Default")
      (node (ref "R32") (pin "2") (pinfunction "2_2") (pintype "passive"))
      (node (ref "SW1") (pin "2") (pinfunction "2_2") (pintype "bidirectional"))
    )
    (net (code "45") (name "Net-(S1-NC)") (class "Default")
      (node (ref "S1") (pin "1") (pinfunction "NC_1") (pintype "passive"))
      (node (ref "SB1") (pin "2") (pinfunction "2_2") (pintype "passive"))
    )
    (net (code "46") (name "Net-(S1-NO)") (class "Default")
      (node (ref "S1") (pin "3") (pinfunction "NO_3") (pintype "passive"))
      (node (ref "SB1") (pin "4") (pinfunction "4_4") (pintype "passive"))
    )
    (net (code "47") (name "Net-(S2-NC)") (class "Default")
      (node (ref "S2") (pin "1") (pinfunction "NC_1") (pintype "passive"))
      (node (ref "SB2") (pin "2") (pinfunction "2_2") (pintype "passive"))
    )
    (net (code "48") (name "Net-(S2-NO)") (class "Default")
      (node (ref "S2") (pin "3") (pinfunction "NO_3") (pintype "passive"))
      (node (ref "SB2") (pin "4") (pinfunction "4_4") (pintype "passive"))
    )
    (net (code "49") (name "Net-(S3-NC)") (class "Default")
      (node (ref "S3") (pin "1") (pinfunction "NC_1") (pintype "passive"))
      (node (ref "SB3") (pin "2") (pinfunction "2_2") (pintype "passive"))
    )
    (net (code "50") (name "Net-(S3-NO)") (class "Default")
      (node (ref "S3") (pin "3") (pinfunction "NO_3") (pintype "passive"))
      (node (ref "SB3") (pin "4") (pinfunction "4_4") (pintype "passive"))
    )
    (net (code "51") (name "Net-(U1-D+)") (class "Default")
      (node (ref "R6") (pin "2") (pinfunction "2_2") (pintype "passive"))
      (node (ref "U1") (pin "1") (pinfunction "D+_1") (pintype "bidirectional"))
    )
    (net (code "52") (name "Net-(U1-D-)") (class "Default")
      (node (ref "R7") (pin "2") (pinfunction "2_2") (pintype "passive"))
      (node (ref "U1") (pin "2") (pinfunction "D-_2") (pintype "bidirectional"))
    )
    (net (code "53") (name "Net-(U1-VCCP1I)") (class "Default")
      (node (ref "C7") (pin "1") (pinfunction "1_1") (pintype "passive"))
      (node (ref "U1") (pin "17") (pinfunction "VCCP1I_17") (pintype "power_in"))
    )
    (net (code "54") (name "Net-(U1-VCCP2I)") (class "Default")
      (node (ref "C8") (pin "1") (pinfunction "1_1") (pintype "passive"))
      (node (ref "U1") (pin "19") (pinfunction "VCCP2I_19") (pintype "power_in"))
    )
    (net (code "55") (name "Net-(U1-VCCXI)") (class "Default")
      (node (ref "C9") (pin "1") (pinfunction "1_1") (pintype "passive"))
      (node (ref "U1") (pin "23") (pinfunction "VCCXI_23") (pintype "power_in"))
    )
    (net (code "56") (name "Net-(U1-VINL)") (class "Default")
      (node (ref "C1") (pin "+") (pinfunction "+_+") (pintype "passive"))
      (node (ref "U1") (pin "12") (pinfunction "VINL_12") (pintype "input"))
    )
    (net (code "57") (name "Net-(U1-VINR)") (class "Default")
      (node (ref "C2") (pin "+") (pinfunction "+_+") (pintype "passive"))
      (node (ref "U1") (pin "13") (pinfunction "VINR_13") (pintype "input"))
    )
    (net (code "58") (name "Net-(U1-VOUTL)") (class "Default")
      (node (ref "C11") (pin "+") (pinfunction "+_+") (pintype "passive"))
      (node (ref "U1") (pin "16") (pinfunction "VOUTL_16") (pintype "output"))
    )
    (net (code "59") (name "Net-(U1-VOUTR)") (class "Default")
      (node (ref "C12") (pin "+") (pinfunction "+_+") (pintype "passive"))
      (node (ref "U1") (pin "15") (pinfunction "VOUTR_15") (pintype "output"))
    )
    (net (code "60") (name "Net-(U1-XTO)") (class "Default")
      (node (ref "C10") (pin "2") (pinfunction "2_2") (pintype "passive"))
      (node (ref "R8") (pin "2") (pinfunction "2_2") (pintype "passive"))
      (node (ref "U1") (pin "20") (pinfunction "XTO_20") (pintype "output"))
      (node (ref "Y1") (pin "1") (pinfunction "1_1") (pintype "passive"))
    )
    (net (code "61") (name "Net-(U1-~{SSPND})") (class "Default")
      (node (ref "R3") (pin "2") (pinfunction "2_2") (pintype "passive"))
      (node (ref "R4") (pin "2") (pinfunction "2_2") (pintype "passive"))
      (node (ref "R5") (pin "2") (pinfunction "2_2") (pintype "passive"))
      (node (ref "U1") (pin "28") (pinfunction "~{SSPND}_28") (pintype "output"))
      (node (ref "U2") (pin "4") (pinfunction "EN_4") (pintype "input"))
    )
    (net (code "62") (name "Net-(U2-FB_NC)") (class "Default")
      (node (ref "R11") (pin "1") (pinfunction "1_1") (pintype "passive"))
      (node (ref "R9") (pin "2") (pinfunction "2_2") (pintype "passive"))
      (node (ref "U2") (pin "2") (pinfunction "FB_NC_2") (pintype "input"))
    )
    (net (code "63") (name "Net-(U5-IN_A-)") (class "Default")
      (node (ref "C36") (pin "2") (pinfunction "2_2") (pintype "passive"))
      (node (ref "R41") (pin "1") (pinfunction "1_1") (pintype "passive"))
      (node (ref "U5") (pin "2") (pinfunction "IN_A-_2") (pintype "input"))
    )
    (net (code "64") (name "Net-(U5-IN_B-)") (class "Default")
      (node (ref "C37") (pin "2") (pinfunction "2_2") (pintype "passive"))
      (node (ref "R42") (pin "1") (pinfunction "1_1") (pintype "passive"))
      (node (ref "U5") (pin "6") (pinfunction "IN_B-_6") (pintype "input"))
    )
    (net (code "65") (name "Net-(U5-OUT_A)") (class "Default")
      (node (ref "C27") (pin "+") (pinfunction "+_+") (pintype "passive"))
      (node (ref "C36") (pin "1") (pinfunction "1_1") (pintype "passive"))
      (node (ref "R37") (pin "1") (pinfunction "1_1") (pintype "passive"))
      (node (ref "U5") (pin "1") (pinfunction "OUT_A_1") (pintype "output"))
    )
    (net (code "66") (name "Net-(U5-OUT_B)") (class "Default")
      (node (ref "C33") (pin "+") (pinfunction "+_+") (pintype "passive"))
      (node (ref "C37") (pin "1") (pinfunction "1_1") (pintype "passive"))
      (node (ref "R39") (pin "1") (pinfunction "1_1") (pintype "passive"))
      (node (ref "U5") (pin "7") (pinfunction "OUT_B_7") (pintype "output"))
    )
    (net (code "67") (name "OUTA1") (class "Default")
      (node (ref "R16") (pin "1") (pinfunction "1_1") (pintype "passive"))
      (node (ref "R17") (pin "1") (pinfunction "1_1") (pintype "passive"))
      (node (ref "R18") (pin "1") (pinfunction "1_1") (pintype "passive"))
      (node (ref "TPOUTA1") (pin "TP") (pinfunction "TP_TP") (pintype "input"))
      (node (ref "U3") (pin "10") (pinfunction "-INA_10") (pintype "input"))
      (node (ref "U3") (pin "9") (pinfunction "OUTA_9") (pintype "output"))
    )
    (net (code "68") (name "OUTA2") (class "Default")
      (node (ref "R33") (pin "2") (pinfunction "2_2") (pintype "passive"))
      (node (ref "TPOUTA2") (pin "TP") (pinfunction "TP_TP") (pintype "input"))
      (node (ref "U4") (pin "10") (pinfunction "-INA_10") (pintype "input"))
      (node (ref "U4") (pin "9") (pinfunction "OUTA_9") (pintype "output"))
    )
    (net (code "69") (name "OUTB1") (class "Default")
      (node (ref "C25") (pin "+") (pinfunction "+_+") (pintype "passive"))
      (node (ref "R25") (pin "2") (pinfunction "2_2") (pintype "passive"))
      (node (ref "R26") (pin "2") (pinfunction "2_2") (pintype "passive"))
      (node (ref "R27") (pin "2") (pinfunction "2_2") (pintype "passive"))
      (node (ref "TPOUTB1") (pin "TP") (pinfunction "TP_TP") (pintype "input"))
      (node (ref "U3") (pin "7") (pinfunction "OUTB_7") (pintype "output"))
    )
    (net (code "70") (name "OUTB2") (class "Default")
      (node (ref "C1") (pin "-") (pinfunction "-_-") (pintype "passive"))
      (node (ref "C28") (pin "2") (pinfunction "2_2") (pintype "passive"))
      (node (ref "R34") (pin "1") (pinfunction "1_1") (pintype "passive"))
      (node (ref "R35") (pin "2") (pinfunction "2_2") (pintype "passive"))
      (node (ref "SJ3") (pin "1") (pinfunction "1_1") (pintype "passive"))
      (node (ref "SW1") (pin "1") (pinfunction "1_1") (pintype "bidirectional"))
      (node (ref "SW1") (pin "4") (pinfunction "4_4") (pintype "bidirectional"))
      (node (ref "TPVINL") (pin "TP") (pinfunction "TP_TP") (pintype "input"))
      (node (ref "U4") (pin "7") (pinfunction "OUTB_7") (pintype "output"))
    )
    (net (code "71") (name "SEL0") (class "Default")
      (node (ref "JP1") (pin "5") (pinfunction "5_5") (pintype "passive"))
      (node (ref "U1") (pin "8") (pinfunction "SEL0_8") (pintype "input"))
    )
    (net (code "72") (name "SEL1") (class "Default")
      (node (ref "JP1") (pin "7") (pinfunction "7_7") (pintype "passive"))
      (node (ref "U1") (pin "9") (pinfunction "SEL1_9") (pintype "input"))
    )
    (net (code "73") (name "VBUS") (class "Default")
      (node (ref "C16") (pin "2") (pinfunction "2_2") (pintype "passive"))
      (node (ref "C3") (pin "1") (pinfunction "1_1") (pintype "passive"))
      (node (ref "R2") (pin "1") (pinfunction "1_1") (pintype "passive"))
      (node (ref "TPVBUS") (pin "TP") (pinfunction "TP_TP") (pintype "input"))
      (node (ref "U2") (pin "6") (pinfunction "IN_6") (pintype "power_in"))
      (node (ref "X1") (pin "1") (pinfunction "1_1") (pintype "passive"))
    )
    (net (code "74") (name "VBUS*") (class "Default")
      (node (ref "C4") (pin "1") (pinfunction "1_1") (pintype "passive"))
      (node (ref "R2") (pin "2") (pinfunction "2_2") (pintype "passive"))
      (node (ref "U1") (pin "3") (pinfunction "VBUS_3") (pintype "bidirectional"))
    )
    (net (code "75") (name "VCCCI") (class "Default")
      (node (ref "C6") (pin "+") (pinfunction "+_+") (pintype "passive"))
      (node (ref "D1") (pin "C") (pinfunction "K_C") (pintype "passive"))
      (node (ref "U1") (pin "10") (pinfunction "VCCCI_10") (pintype "power_in"))
    )
    (net (code "76") (name "VCOM") (class "Default")
      (node (ref "C24") (pin "1") (pinfunction "1_1") (pintype "passive"))
      (node (ref "C34") (pin "2") (pinfunction "2_2") (pintype "passive"))
      (node (ref "C5") (pin "+") (pinfunction "+_+") (pintype "passive"))
      (node (ref "R15") (pin "1") (pinfunction "1_1") (pintype "passive"))
      (node (ref "R29") (pin "1") (pinfunction "1_1") (pintype "passive"))
      (node (ref "SJ1") (pin "1") (pinfunction "1_1") (pintype "passive"))
      (node (ref "SJ4") (pin "1") (pinfunction "1_1") (pintype "passive"))
      (node (ref "TPVCOM") (pin "TP") (pinfunction "TP_TP") (pintype "input"))
      (node (ref "U1") (pin "14") (pinfunction "VCOM_14") (pintype "bidirectional"))
      (node (ref "U5") (pin "3") (pinfunction "IN_A+_3") (pintype "input"))
      (node (ref "U5") (pin "5") (pinfunction "IN_B+_5") (pintype "input"))
    )
    (net (code "77") (name "VDD") (class "Default")
      (node (ref "C13") (pin "1") (pinfunction "1_1") (pintype "passive"))
      (node (ref "JP1") (pin "6") (pinfunction "6_6") (pintype "passive"))
      (node (ref "JP1") (pin "8") (pinfunction "8_8") (pintype "passive"))
      (node (ref "R1") (pin "2") (pinfunction "2_2") (pintype "passive"))
      (node (ref "U1") (pin "27") (pinfunction "VDD_27") (pintype "power_in"))
    )
    (net (code "78") (name "VOLD") (class "Default")
      (node (ref "S1") (pin "2") (pinfunction "COM_2") (pintype "passive"))
      (node (ref "U1") (pin "7") (pinfunction "HID2_7") (pintype "input"))
    )
    (net (code "79") (name "VOLU") (class "Default")
      (node (ref "S2") (pin "2") (pinfunction "COM_2") (pintype "passive"))
      (node (ref "U1") (pin "6") (pinfunction "HID1_6") (pintype "input"))
    )
    (net (code "80") (name "VOUTL") (class "Default")
      (node (ref "C11") (pin "-") (pinfunction "-_-") (pintype "passive"))
      (node (ref "SW1") (pin "6") (pinfunction "6_6") (pintype "bidirectional"))
      (node (ref "TPVOUTL") (pin "TP") (pinfunction "TP_TP") (pintype "input"))
    )
    (net (code "81") (name "VOUTR") (class "Default")
      (node (ref "C12") (pin "-") (pinfunction "-_-") (pintype "passive"))
      (node (ref "SW1") (pin "3") (pinfunction "3_3") (pintype "bidirectional"))
      (node (ref "TPVOUTR") (pin "TP") (pinfunction "TP_TP") (pintype "input"))
    )
    (net (code "82") (name "VREG") (class "Default")
      (node (ref "C15") (pin "2") (pinfunction "2_2") (pintype "passive"))
      (node (ref "C19") (pin "1") (pinfunction "1_1") (pintype "passive"))
      (node (ref "C26") (pin "1") (pinfunction "1_1") (pintype "passive"))
      (node (ref "C30") (pin "+") (pinfunction "+_+") (pintype "passive"))
      (node (ref "C31") (pin "1") (pinfunction "1_1") (pintype "passive"))
      (node (ref "C32") (pin "1") (pinfunction "1_1") (pintype "passive"))
      (node (ref "IC1") (pin "5") (pinfunction "V+_5") (pintype "power_in"))
      (node (ref "JP1") (pin "10") (pinfunction "10_10") (pintype "passive"))
      (node (ref "R10") (pin "2") (pinfunction "2_2") (pintype "passive"))
      (node (ref "R11") (pin "2") (pinfunction "2_2") (pintype "passive"))
      (node (ref "R23") (pin "1") (pinfunction "1_1") (pintype "passive"))
      (node (ref "R38") (pin "3") (pinfunction "E_3") (pintype "passive"))
      (node (ref "R40") (pin "2") (pinfunction "2_2") (pintype "passive"))
      (node (ref "TPVREG") (pin "TP") (pinfunction "TP_TP") (pintype "input"))
      (node (ref "U2") (pin "1") (pinfunction "OUT_1") (pintype "power_in"))
      (node (ref "U3") (pin "2") (pinfunction "V+_2") (pintype "power_in"))
      (node (ref "U4") (pin "2") (pinfunction "V+_2") (pintype "power_in"))
      (node (ref "U5") (pin "8") (pinfunction "VDD_8") (pintype "power_in"))
    )
    (net (code "83") (name "XTI") (class "Default")
      (node (ref "C14") (pin "2") (pinfunction "2_2") (pintype "passive"))
      (node (ref "R8") (pin "1") (pinfunction "1_1") (pintype "passive"))
      (node (ref "U1") (pin "21") (pinfunction "XTI_21") (pintype "input"))
      (node (ref "Y1") (pin "2") (pinfunction "2_2") (pintype "passive"))
    )
    (net (code "84") (name "unconnected-(U2-PG-Pad3)") (class "Default")
      (node (ref "U2") (pin "3") (pinfunction "PG_3") (pintype "open_collector"))
    )
  )
)
